# USB_Connector.net
KiCad netlist of a schematic drawn in Altium Designer
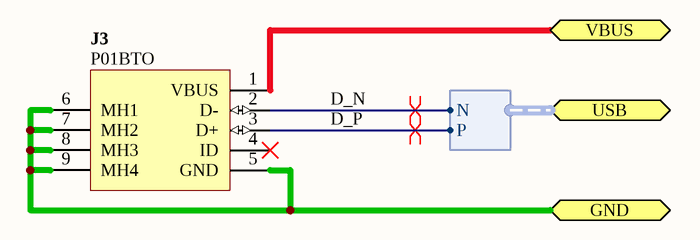
[diagram p0: USB_Connector.SchDoc]

(export (version "E")
  (design (tool "Eeschema 10.0.6"))
  (components
    (comp (ref "J3")
      (value "P01BTO")
      (footprint "Qiwei-SMD")
      (description "Connector Mini USB, Right Angle, Receptacle")
      (libsource (lib "Altium Content Vault") (part "CMP-5172-00001-1"))
    )
  )
  (nets
    (net (code "2") (name "/D_N") (class "Default")
      (node (ref "J3") (pin "2") (pinfunction "D-_2") (pintype "bidirectional"))
    )
    (net (code "3") (name "/D_P") (class "Default")
      (node (ref "J3") (pin "3") (pinfunction "D+_3") (pintype "bidirectional"))
    )
    (net (code "4") (name "/GND") (class "Default")
      (node (ref "J3") (pin "5") (pinfunction "GND_5") (pintype "power_in"))
      (node (ref "J3") (pin "6") (pinfunction "MH1_6") (pintype "passive"))
      (node (ref "J3") (pin "7") (pinfunction "MH2_7") (pintype "passive"))
      (node (ref "J3") (pin "8") (pinfunction "MH3_8") (pintype "passive"))
      (node (ref "J3") (pin "9") (pinfunction "MH4_9") (pintype "passive"))
    )
    (net (code "5") (name "/VBUS") (class "Default")
      (node (ref "J3") (pin "1") (pinfunction "VBUS_1") (pintype "power_in"))
    )
    (net (code "7") (name "unconnected-(J3-ID-Pad4)") (class "Default")
      (node (ref "J3") (pin "4") (pinfunction "ID_4") (pintype "passive+no_connect"))
    )
  )
)
